# Control_and_inputs.net
KiCad netlist of a schematic drawn in Altium Designer
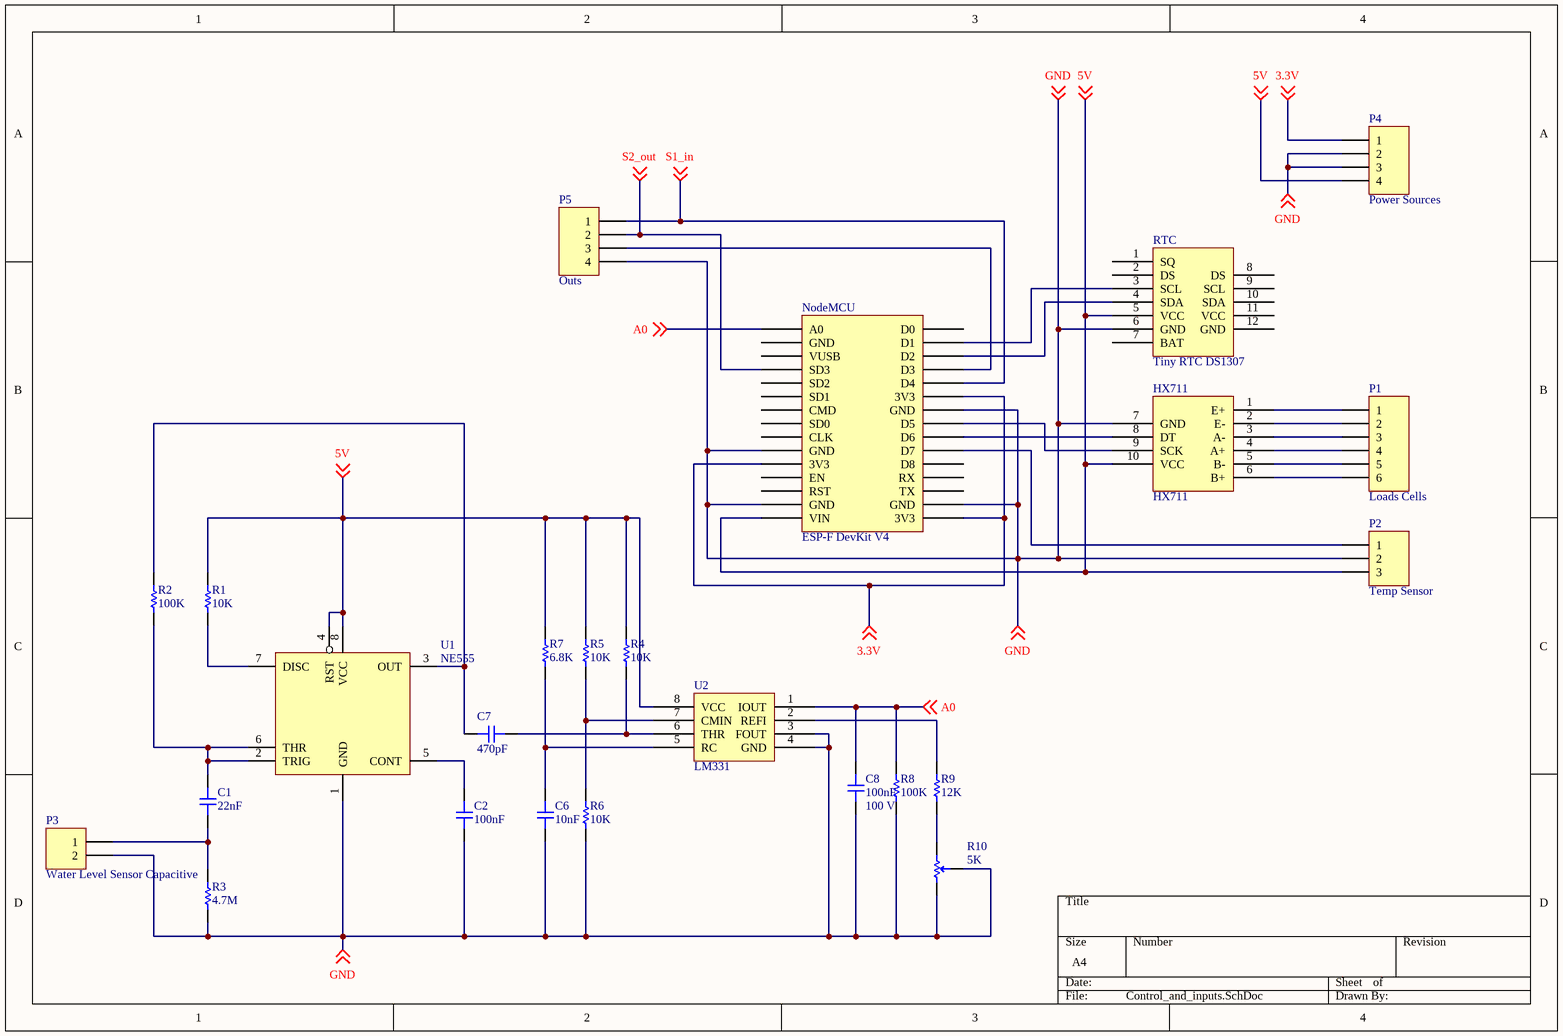
[diagram p0: Control_and_inputs.SchDoc]

(export (version "E")
  (design (tool "Eeschema 10.0.6"))
  (components
    (comp (ref "C1")
      (value "22nF")
      (footprint "C200-350-150")
      (description "Capacitor")
      (fields (field (name "VOLTAGE") "100 V") (field (name "PUBLISHER") "Altium Limited"))
      (libsource (lib "lib_GPDSE") (part "Capacitor"))
    )
    (comp (ref "C2")
      (value "100nF")
      (footprint "C200-350-150")
      (description "Capacitor")
      (fields (field (name "VOLTAGE") "100 V") (field (name "PUBLISHER") "Altium Limited"))
      (libsource (lib "lib_GPDSE") (part "Capacitor"))
    )
    (comp (ref "C6")
      (value "10nF")
      (footprint "C200-350-150")
      (description "Capacitor")
      (fields (field (name "VOLTAGE") "100 V") (field (name "PUBLISHER") "Altium Limited"))
      (libsource (lib "lib_GPDSE") (part "Capacitor"))
    )
    (comp (ref "C7")
      (value "470pF")
      (footprint "C200-350-150")
      (description "Capacitor")
      (fields (field (name "VOLTAGE") "100 V") (field (name "PUBLISHER") "Altium Limited"))
      (libsource (lib "lib_GPDSE") (part "Capacitor"))
    )
    (comp (ref "C8")
      (value "100nF")
      (footprint "C200-350-150")
      (description "Capacitor")
      (fields (field (name "VOLTAGE") "100 V") (field (name "PUBLISHER") "Altium Limited"))
      (libsource (lib "lib_GPDSE") (part "Capacitor"))
    )
    (comp (ref "HX711") (value "HX711") (footprint "HX711") (libsource (lib "Schlib1") (part "HX711")))
    (comp (ref "NodeMCU")
      (value "ESP-F DevKit V4")
      (footprint "LoLin (+ NodeMCU)")
      (libsource (lib "nodemcu") (part "NodeMCU V1.0 ESP-12E_1"))
    )
    (comp (ref "P1")
      (value "Loads Cells")
      (footprint "KRE_6")
      (description "Terminal Block 1x6")
      (libsource (lib "lib_GPDSE") (part "KRE_6"))
    )
    (comp (ref "P2")
      (value "Temp Sensor")
      (footprint "KRE_3")
      (description "Terminal Block 1x3")
      (libsource (lib "lib_GPDSE") (part "KRE_3"))
    )
    (comp (ref "P3")
      (value "Water Level Sensor Capacitive")
      (footprint "KRE_2")
      (description "Terminal Block 1x2")
      (libsource (lib "lib_GPDSE") (part "KRE_2"))
    )
    (comp (ref "P4")
      (value "Power Sources")
      (footprint "KRE_4")
      (description "Terminal Block 1x4")
      (libsource (lib "lib_GPDSE") (part "KRE_4"))
    )
    (comp (ref "P5")
      (value "Outs")
      (footprint "KRE_4")
      (description "Terminal Block 1x4")
      (libsource (lib "") (part "KRE_4_1"))
    )
    (comp (ref "R1")
      (value "10K")
      (footprint "R400-2.0mm")
      (description "Resistor")
      (fields
        (field (name "TOLERANCE") "5%")
        (field (name "POWER") "1/4 W")
        (field (name "PUBLISHER") "Altium Limited")
      )
      (libsource (lib "lib_GPDSE") (part "Resistor"))
    )
    (comp (ref "R2")
      (value "100K")
      (footprint "R400-2.0mm")
      (description "Resistor")
      (fields
        (field (name "TOLERANCE") "5%")
        (field (name "POWER") "1/4 W")
        (field (name "PUBLISHER") "Altium Limited")
      )
      (libsource (lib "lib_GPDSE") (part "Resistor"))
    )
    (comp (ref "R3")
      (value "4.7M")
      (footprint "R400-2.0mm")
      (description "Resistor")
      (fields
        (field (name "TOLERANCE") "5%")
        (field (name "POWER") "1/4 W")
        (field (name "PUBLISHER") "Altium Limited")
      )
      (libsource (lib "lib_GPDSE") (part "Resistor"))
    )
    (comp (ref "R4")
      (value "10K")
      (footprint "R400-2.0mm")
      (description "Resistor")
      (fields
        (field (name "TOLERANCE") "5%")
        (field (name "POWER") "1/4 W")
        (field (name "PUBLISHER") "Altium Limited")
      )
      (libsource (lib "lib_GPDSE") (part "Resistor"))
    )
    (comp (ref "R5")
      (value "10K")
      (footprint "R400-2.0mm")
      (description "Resistor")
      (fields
        (field (name "TOLERANCE") "5%")
        (field (name "POWER") "1/4 W")
        (field (name "PUBLISHER") "Altium Limited")
      )
      (libsource (lib "lib_GPDSE") (part "Resistor"))
    )
    (comp (ref "R6")
      (value "10K")
      (footprint "R400-2.0mm")
      (description "Resistor")
      (fields
        (field (name "TOLERANCE") "5%")
        (field (name "POWER") "1/4 W")
        (field (name "PUBLISHER") "Altium Limited")
      )
      (libsource (lib "lib_GPDSE") (part "Resistor"))
    )
    (comp (ref "R7")
      (value "6.8K")
      (footprint "R400-2.0mm")
      (description "Resistor")
      (fields
        (field (name "TOLERANCE") "5%")
        (field (name "POWER") "1/4 W")
        (field (name "PUBLISHER") "Altium Limited")
      )
      (libsource (lib "lib_GPDSE") (part "Resistor"))
    )
    (comp (ref "R8")
      (value "100K")
      (footprint "R400-2.0mm")
      (description "Resistor")
      (fields
        (field (name "TOLERANCE") "5%")
        (field (name "POWER") "1/4 W")
        (field (name "PUBLISHER") "Altium Limited")
      )
      (libsource (lib "lib_GPDSE") (part "Resistor"))
    )
    (comp (ref "R9")
      (value "12K")
      (footprint "R400-2.0mm")
      (description "Resistor")
      (fields
        (field (name "TOLERANCE") "5%")
        (field (name "POWER") "1/4 W")
        (field (name "PUBLISHER") "Altium Limited")
      )
      (libsource (lib "lib_GPDSE") (part "Resistor"))
    )
    (comp (ref "R10")
      (value "5K")
      (footprint "Trimpot-3260W")
      (description "Trimpot")
      (libsource (lib "lib_GPDSE") (part "Trimpot"))
    )
    (comp (ref "RTC")
      (value "Tiny RTC DS1307")
      (footprint "TinyRTC")
      (libsource (lib "Schlib1") (part "Tiny RTC DS1307"))
    )
    (comp (ref "U1")
      (value "NE555")
      (footprint "DIP08-300(100)")
      (description "NE555 Precision Timers")
      (libsource (lib "lib_GPDSE") (part "NE555"))
    )
    (comp (ref "U2") (value "LM331") (footprint "DIP08-300(100)") (libsource (lib "Schlib1") (part "LM331")))
  )
  (nets
    (net (code "1") (name "3.3V") (class "Default")
      (node (ref "NodeMCU") (pin "3V3") (pinfunction "3V3_3V3") (pintype "passive"))
      (node (ref "P4") (pin "1") (pinfunction "1_1") (pintype "passive"))
    )
    (net (code "2") (name "5V") (class "Default")
      (node (ref "HX711") (pin "10") (pinfunction "VCC_10") (pintype "passive"))
      (node (ref "NodeMCU") (pin "VIN") (pinfunction "VIN_VIN") (pintype "passive"))
      (node (ref "P2") (pin "3") (pinfunction "3_3") (pintype "passive"))
      (node (ref "P4") (pin "4") (pinfunction "4_4") (pintype "passive"))
      (node (ref "R1") (pin "2") (pinfunction "2_2") (pintype "passive"))
      (node (ref "R4") (pin "2") (pinfunction "2_2") (pintype "passive"))
      (node (ref "R5") (pin "2") (pinfunction "2_2") (pintype "passive"))
      (node (ref "R7") (pin "2") (pinfunction "2_2") (pintype "passive"))
      (node (ref "RTC") (pin "5") (pinfunction "VCC_5") (pintype "passive"))
      (node (ref "U1") (pin "4") (pinfunction "RST_4") (pintype "passive"))
      (node (ref "U1") (pin "8") (pinfunction "VCC_8") (pintype "power_in"))
      (node (ref "U2") (pin "8") (pinfunction "VCC_8") (pintype "passive"))
    )
    (net (code "3") (name "A0") (class "Default")
      (node (ref "C8") (pin "2") (pinfunction "2_2") (pintype "passive"))
      (node (ref "NodeMCU") (pin "A0") (pinfunction "A0_A0") (pintype "passive"))
      (node (ref "R8") (pin "2") (pinfunction "2_2") (pintype "passive"))
      (node (ref "U2") (pin "1") (pinfunction "IOUT_1") (pintype "passive"))
    )
    (net (code "4") (name "GND") (class "Default")
      (node (ref "C2") (pin "1") (pinfunction "1_1") (pintype "passive"))
      (node (ref "C6") (pin "1") (pinfunction "1_1") (pintype "passive"))
      (node (ref "C8") (pin "1") (pinfunction "1_1") (pintype "passive"))
      (node (ref "HX711") (pin "7") (pinfunction "GND_7") (pintype "passive"))
      (node (ref "NodeMCU") (pin "GND") (pinfunction "GND_GND") (pintype "passive"))
      (node (ref "P2") (pin "2") (pinfunction "2_2") (pintype "passive"))
      (node (ref "P3") (pin "2") (pinfunction "2_2") (pintype "passive"))
      (node (ref "P4") (pin "2") (pinfunction "2_2") (pintype "passive"))
      (node (ref "P4") (pin "3") (pinfunction "3_3") (pintype "passive"))
      (node (ref "P5") (pin "4") (pinfunction "4_4") (pintype "passive"))
      (node (ref "R10") (pin "2") (pinfunction "2_2") (pintype "passive"))
      (node (ref "R10") (pin "3") (pinfunction "3_3") (pintype "passive"))
      (node (ref "R3") (pin "1") (pinfunction "1_1") (pintype "passive"))
      (node (ref "R6") (pin "1") (pinfunction "1_1") (pintype "passive"))
      (node (ref "R8") (pin "1") (pinfunction "1_1") (pintype "passive"))
      (node (ref "RTC") (pin "6") (pinfunction "GND_6") (pintype "passive"))
      (node (ref "U1") (pin "1") (pinfunction "GND_1") (pintype "power_in"))
      (node (ref "U2") (pin "3") (pinfunction "FOUT_3") (pintype "passive"))
      (node (ref "U2") (pin "4") (pinfunction "GND_4") (pintype "passive"))
    )
    (net (code "5") (name "Net-(C1-Pad1)") (class "Default")
      (node (ref "C1") (pin "1") (pinfunction "1_1") (pintype "passive"))
      (node (ref "P3") (pin "1") (pinfunction "1_1") (pintype "passive"))
      (node (ref "R3") (pin "2") (pinfunction "2_2") (pintype "passive"))
    )
    (net (code "6") (name "Net-(HX711-A+)") (class "Default")
      (node (ref "HX711") (pin "4") (pinfunction "A+_4") (pintype "passive"))
      (node (ref "P1") (pin "4") (pinfunction "4_4") (pintype "passive"))
    )
    (net (code "7") (name "Net-(HX711-A-)") (class "Default")
      (node (ref "HX711") (pin "3") (pinfunction "A-_3") (pintype "passive"))
      (node (ref "P1") (pin "3") (pinfunction "3_3") (pintype "passive"))
    )
    (net (code "8") (name "Net-(HX711-B+)") (class "Default")
      (node (ref "HX711") (pin "6") (pinfunction "B+_6") (pintype "passive"))
      (node (ref "P1") (pin "6") (pinfunction "6_6") (pintype "passive"))
    )
    (net (code "9") (name "Net-(HX711-B-)") (class "Default")
      (node (ref "HX711") (pin "5") (pinfunction "B-_5") (pintype "passive"))
      (node (ref "P1") (pin "5") (pinfunction "5_5") (pintype "passive"))
    )
    (net (code "10") (name "Net-(HX711-DT)") (class "Default")
      (node (ref "HX711") (pin "8") (pinfunction "DT_8") (pintype "passive"))
      (node (ref "NodeMCU") (pin "D6") (pinfunction "D6_D6") (pintype "passive"))
    )
    (net (code "11") (name "Net-(HX711-E+)") (class "Default")
      (node (ref "HX711") (pin "1") (pinfunction "E+_1") (pintype "passive"))
      (node (ref "P1") (pin "1") (pinfunction "1_1") (pintype "passive"))
    )
    (net (code "12") (name "Net-(HX711-E-)") (class "Default")
      (node (ref "HX711") (pin "2") (pinfunction "E-_2") (pintype "passive"))
      (node (ref "P1") (pin "2") (pinfunction "2_2") (pintype "passive"))
    )
    (net (code "13") (name "Net-(HX711-SCK)") (class "Default")
      (node (ref "HX711") (pin "9") (pinfunction "SCK_9") (pintype "passive"))
      (node (ref "NodeMCU") (pin "D5") (pinfunction "D5_D5") (pintype "passive"))
    )
    (net (code "14") (name "Net-(NodeMCU-PadD1)") (class "Default")
      (node (ref "NodeMCU") (pin "D1") (pinfunction "D1_D1") (pintype "passive"))
      (node (ref "RTC") (pin "3") (pinfunction "SCL_3") (pintype "passive"))
    )
    (net (code "15") (name "Net-(NodeMCU-PadD2)") (class "Default")
      (node (ref "NodeMCU") (pin "D2") (pinfunction "D2_D2") (pintype "passive"))
      (node (ref "RTC") (pin "4") (pinfunction "SDA_4") (pintype "passive"))
    )
    (net (code "16") (name "Net-(NodeMCU-PadD3)") (class "Default")
      (node (ref "NodeMCU") (pin "D3") (pinfunction "D3_D3") (pintype "passive"))
      (node (ref "P5") (pin "3") (pinfunction "3_3") (pintype "passive"))
    )
    (net (code "17") (name "Net-(NodeMCU-PadD7)") (class "Default")
      (node (ref "NodeMCU") (pin "D7") (pinfunction "D7_D7") (pintype "passive"))
      (node (ref "P2") (pin "1") (pinfunction "1_1") (pintype "passive"))
    )
    (net (code "18") (name "Net-(R10-Pad1)") (class "Default")
      (node (ref "R10") (pin "1") (pinfunction "1_1") (pintype "passive"))
      (node (ref "R9") (pin "1") (pinfunction "1_1") (pintype "passive"))
    )
    (net (code "19") (name "Net-(U1-CONT)") (class "Default")
      (node (ref "C2") (pin "2") (pinfunction "2_2") (pintype "passive"))
      (node (ref "U1") (pin "5") (pinfunction "CONT_5") (pintype "passive"))
    )
    (net (code "20") (name "Net-(U1-DISC)") (class "Default")
      (node (ref "R1") (pin "1") (pinfunction "1_1") (pintype "passive"))
      (node (ref "U1") (pin "7") (pinfunction "DISC_7") (pintype "open_collector"))
    )
    (net (code "21") (name "Net-(U1-OUT)") (class "Default")
      (node (ref "C7") (pin "2") (pinfunction "2_2") (pintype "passive"))
      (node (ref "R2") (pin "2") (pinfunction "2_2") (pintype "passive"))
      (node (ref "U1") (pin "3") (pinfunction "OUT_3") (pintype "passive"))
    )
    (net (code "22") (name "Net-(U1-THR)") (class "Default")
      (node (ref "C1") (pin "2") (pinfunction "2_2") (pintype "passive"))
      (node (ref "R2") (pin "1") (pinfunction "1_1") (pintype "passive"))
      (node (ref "U1") (pin "2") (pinfunction "TRIG_2") (pintype "passive"))
      (node (ref "U1") (pin "6") (pinfunction "THR_6") (pintype "passive"))
    )
    (net (code "23") (name "Net-(U2-CMIN)") (class "Default")
      (node (ref "R5") (pin "1") (pinfunction "1_1") (pintype "passive"))
      (node (ref "R6") (pin "2") (pinfunction "2_2") (pintype "passive"))
      (node (ref "U2") (pin "7") (pinfunction "CMIN_7") (pintype "passive"))
    )
    (net (code "24") (name "Net-(U2-RC)") (class "Default")
      (node (ref "C6") (pin "2") (pinfunction "2_2") (pintype "passive"))
      (node (ref "R7") (pin "1") (pinfunction "1_1") (pintype "passive"))
      (node (ref "U2") (pin "5") (pinfunction "RC_5") (pintype "passive"))
    )
    (net (code "25") (name "Net-(U2-REFI)") (class "Default")
      (node (ref "R9") (pin "2") (pinfunction "2_2") (pintype "passive"))
      (node (ref "U2") (pin "2") (pinfunction "REFI_2") (pintype "passive"))
    )
    (net (code "26") (name "Net-(U2-THR)") (class "Default")
      (node (ref "C7") (pin "1") (pinfunction "1_1") (pintype "passive"))
      (node (ref "R4") (pin "1") (pinfunction "1_1") (pintype "passive"))
      (node (ref "U2") (pin "6") (pinfunction "THR_6") (pintype "passive"))
    )
    (net (code "27") (name "S1_in") (class "Default")
      (node (ref "NodeMCU") (pin "D4") (pinfunction "D4_D4") (pintype "passive"))
      (node (ref "P5") (pin "1") (pinfunction "1_1") (pintype "passive"))
    )
    (net (code "28") (name "S2_out") (class "Default")
      (node (ref "NodeMCU") (pin "SD3") (pinfunction "SD3_SD3") (pintype "passive"))
      (node (ref "P5") (pin "2") (pinfunction "2_2") (pintype "passive"))
    )
    (net (code "29") (name "unconnected-(NodeMCU-PadCLK)") (class "Default")
      (node (ref "NodeMCU") (pin "CLK") (pinfunction "CLK_CLK") (pintype "passive"))
    )
    (net (code "30") (name "unconnected-(NodeMCU-PadCMD)") (class "Default")
      (node (ref "NodeMCU") (pin "CMD") (pinfunction "CMD_CMD") (pintype "passive"))
    )
    (net (code "31") (name "unconnected-(NodeMCU-PadD0)") (class "Default")
      (node (ref "NodeMCU") (pin "D0") (pinfunction "D0_D0") (pintype "passive"))
    )
    (net (code "32") (name "unconnected-(NodeMCU-PadD8)") (class "Default")
      (node (ref "NodeMCU") (pin "D8") (pinfunction "D8_D8") (pintype "passive"))
    )
    (net (code "33") (name "unconnected-(NodeMCU-PadEN)") (class "Default")
      (node (ref "NodeMCU") (pin "EN") (pinfunction "EN_EN") (pintype "passive"))
    )
    (net (code "34") (name "unconnected-(NodeMCU-PadGND)") (class "Default")
      (node (ref "NodeMCU") (pin "GND") (pinfunction "GND_GND") (pintype "passive"))
    )
    (net (code "35") (name "unconnected-(NodeMCU-PadRST)") (class "Default")
      (node (ref "NodeMCU") (pin "RST") (pinfunction "RST_RST") (pintype "passive"))
    )
    (net (code "36") (name "unconnected-(NodeMCU-PadRX)") (class "Default")
      (node (ref "NodeMCU") (pin "RX") (pinfunction "RX_RX") (pintype "passive"))
    )
    (net (code "37") (name "unconnected-(NodeMCU-PadSD0)") (class "Default")
      (node (ref "NodeMCU") (pin "SD0") (pinfunction "SD0_SD0") (pintype "passive"))
    )
    (net (code "38") (name "unconnected-(NodeMCU-PadSD1)") (class "Default")
      (node (ref "NodeMCU") (pin "SD1") (pinfunction "SD1_SD1") (pintype "passive"))
    )
    (net (code "39") (name "unconnected-(NodeMCU-PadSD2)") (class "Default")
      (node (ref "NodeMCU") (pin "SD2") (pinfunction "SD2_SD2") (pintype "passive"))
    )
    (net (code "40") (name "unconnected-(NodeMCU-PadTX)") (class "Default")
      (node (ref "NodeMCU") (pin "TX") (pinfunction "TX_TX") (pintype "passive"))
    )
    (net (code "41") (name "unconnected-(NodeMCU-PadVUSB)") (class "Default")
      (node (ref "NodeMCU") (pin "VUSB") (pinfunction "VUSB_VUSB") (pintype "passive"))
    )
    (net (code "42") (name "unconnected-(RTC-BAT-Pad7)") (class "Default")
      (node (ref "RTC") (pin "7") (pinfunction "BAT_7") (pintype "passive"))
    )
    (net (code "43") (name "unconnected-(RTC-DS-Pad2)") (class "Default")
      (node (ref "RTC") (pin "2") (pinfunction "DS_2") (pintype "passive"))
    )
    (net (code "44") (name "unconnected-(RTC-DS-Pad8)") (class "Default")
      (node (ref "RTC") (pin "8") (pinfunction "DS_8") (pintype "passive"))
    )
    (net (code "45") (name "unconnected-(RTC-GND-Pad12)") (class "Default")
      (node (ref "RTC") (pin "12") (pinfunction "GND_12") (pintype "passive"))
    )
    (net (code "46") (name "unconnected-(RTC-SCL-Pad9)") (class "Default")
      (node (ref "RTC") (pin "9") (pinfunction "SCL_9") (pintype "passive"))
    )
    (net (code "47") (name "unconnected-(RTC-SDA-Pad10)") (class "Default")
      (node (ref "RTC") (pin "10") (pinfunction "SDA_10") (pintype "passive"))
    )
    (net (code "48") (name "unconnected-(RTC-SQ-Pad1)") (class "Default")
      (node (ref "RTC") (pin "1") (pinfunction "SQ_1") (pintype "passive"))
    )
    (net (code "49") (name "unconnected-(RTC-VCC-Pad11)") (class "Default")
      (node (ref "RTC") (pin "11") (pinfunction "VCC_11") (pintype "passive"))
    )
  )
)
